# valve_schematic.net
KiCad netlist of a schematic drawn in Altium Designer
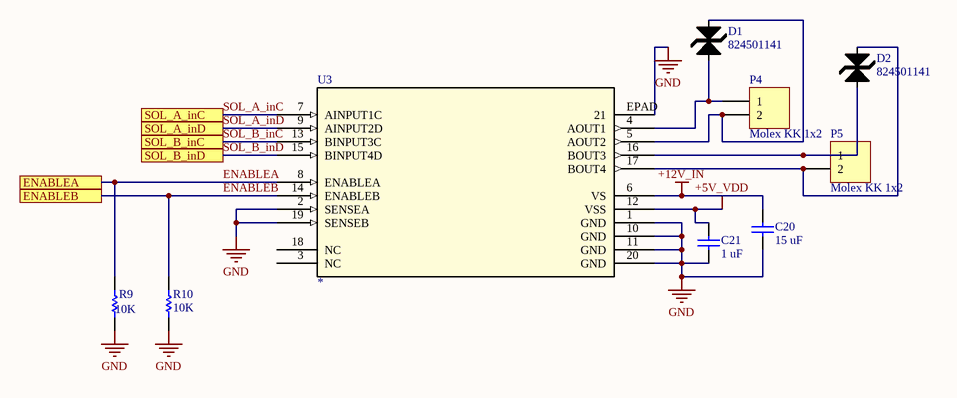
[diagram p0: valve_schematic.SchDoc]

(export (version "E")
  (design (tool "Eeschema 10.0.6"))
  (components
    (comp (ref "C20")
      (value "15 uF")
      (footprint "C0603")
      (description "0603 Capacitor")
      (libsource (lib "PARSEC") (part "C0603"))
    )
    (comp (ref "C21")
      (value "1 uF")
      (footprint "C0603")
      (description "0603 Capacitor")
      (libsource (lib "PARSEC") (part "C0603"))
    )
    (comp (ref "D1")
      (value "824501141")
      (footprint "DIODE-SMA")
      (description "TVS DIODE 14V 23.2V DO214AC")
      (libsource (lib "PARSEC") (part "824501141"))
    )
    (comp (ref "D2")
      (value "824501141")
      (footprint "DIODE-SMA")
      (description "TVS DIODE 14V 23.2V DO214AC")
      (libsource (lib "PARSEC") (part "824501141"))
    )
    (comp (ref "P4")
      (value "Molex KK 1x2")
      (footprint "Molex KK 2x1")
      (description "1x2 Molex KK Connector")
      (libsource (lib "PARSEC") (part "Molex KK 1x2"))
    )
    (comp (ref "P5")
      (value "Molex KK 1x2")
      (footprint "Molex KK 2x1")
      (description "1x2 Molex KK Connector")
      (libsource (lib "PARSEC") (part "Molex KK 1x2"))
    )
    (comp (ref "R9")
      (value "10K")
      (footprint "R0805")
      (description "RESISTOR 0805")
      (libsource (lib "PARSEC(1)") (part "R0805"))
    )
    (comp (ref "R10")
      (value "10K")
      (footprint "R0805")
      (description "RESISTOR 0805")
      (libsource (lib "PARSEC(1)") (part "R0805"))
    )
    (comp (ref "U3")
      (value "*")
      (footprint "PowerSO-20")
      (description "Imported")
      (fields (field (name "MANUFACTURER_PART_NUMBER") "L298P013TR"))
      (libsource (lib "PARSEC(1)") (part "L298P013TR"))
    )
  )
  (nets
    (net (code "1") (name "+5V_VDD") (class "Default")
      (node (ref "C21") (pin "1") (pinfunction "1_1") (pintype "passive"))
      (node (ref "U3") (pin "12") (pinfunction "VSS_12") (pintype "power_in"))
    )
    (net (code "2") (name "+12V_IN") (class "Default")
      (node (ref "C20") (pin "1") (pinfunction "1_1") (pintype "passive"))
      (node (ref "U3") (pin "6") (pinfunction "VS_6") (pintype "power_in"))
    )
    (net (code "3") (name "/ENABLEA") (class "Default")
      (node (ref "R9") (pin "2") (pinfunction "2_2") (pintype "passive"))
      (node (ref "U3") (pin "8") (pinfunction "ENABLEA_8") (pintype "input"))
    )
    (net (code "4") (name "/ENABLEB") (class "Default")
      (node (ref "R10") (pin "2") (pinfunction "2_2") (pintype "passive"))
      (node (ref "U3") (pin "14") (pinfunction "ENABLEB_14") (pintype "input"))
    )
    (net (code "5") (name "/SOL_A_inC") (class "Default")
      (node (ref "U3") (pin "7") (pinfunction "AINPUT1C_7") (pintype "input"))
    )
    (net (code "6") (name "/SOL_A_inD") (class "Default")
      (node (ref "U3") (pin "9") (pinfunction "AINPUT2D_9") (pintype "input"))
    )
    (net (code "7") (name "/SOL_B_inC") (class "Default")
      (node (ref "U3") (pin "13") (pinfunction "BINPUT3C_13") (pintype "input"))
    )
    (net (code "8") (name "/SOL_B_inD") (class "Default")
      (node (ref "U3") (pin "15") (pinfunction "BINPUT4D_15") (pintype "input"))
    )
    (net (code "9") (name "GND") (class "Default")
      (node (ref "C20") (pin "2") (pinfunction "2_2") (pintype "passive"))
      (node (ref "C21") (pin "2") (pinfunction "2_2") (pintype "passive"))
      (node (ref "R10") (pin "1") (pinfunction "1_1") (pintype "passive"))
      (node (ref "R9") (pin "1") (pinfunction "1_1") (pintype "passive"))
      (node (ref "U3") (pin "1") (pinfunction "GND_1") (pintype "passive"))
      (node (ref "U3") (pin "10") (pinfunction "GND_10") (pintype "passive"))
      (node (ref "U3") (pin "11") (pinfunction "GND_11") (pintype "passive"))
      (node (ref "U3") (pin "19") (pinfunction "SENSEB_19") (pintype "input"))
      (node (ref "U3") (pin "2") (pinfunction "SENSEA_2") (pintype "input"))
      (node (ref "U3") (pin "20") (pinfunction "GND_20") (pintype "passive"))
      (node (ref "U3") (pin "EPAD") (pinfunction "21_EPAD") (pintype "passive"))
    )
    (net (code "10") (name "Net-(U3-AOUT1)") (class "Default")
      (node (ref "D1") (pin "A") (pinfunction "A_A") (pintype "passive"))
      (node (ref "P4") (pin "1") (pinfunction "1_1") (pintype "passive"))
      (node (ref "U3") (pin "4") (pinfunction "AOUT1_4") (pintype "output"))
    )
    (net (code "11") (name "Net-(U3-AOUT2)") (class "Default")
      (node (ref "D1") (pin "K") (pinfunction "K_K") (pintype "passive"))
      (node (ref "P4") (pin "2") (pinfunction "2_2") (pintype "passive"))
      (node (ref "U3") (pin "5") (pinfunction "AOUT2_5") (pintype "output"))
    )
    (net (code "12") (name "Net-(U3-BOUT3)") (class "Default")
      (node (ref "D2") (pin "A") (pinfunction "A_A") (pintype "passive"))
      (node (ref "P5") (pin "1") (pinfunction "1_1") (pintype "passive"))
      (node (ref "U3") (pin "16") (pinfunction "BOUT3_16") (pintype "output"))
    )
    (net (code "13") (name "Net-(U3-BOUT4)") (class "Default")
      (node (ref "D2") (pin "K") (pinfunction "K_K") (pintype "passive"))
      (node (ref "P5") (pin "2") (pinfunction "2_2") (pintype "passive"))
      (node (ref "U3") (pin "17") (pinfunction "BOUT4_17") (pintype "output"))
    )
    (net (code "14") (name "unconnected-(U3-NC-Pad3)") (class "Default")
      (node (ref "U3") (pin "3") (pinfunction "NC_3") (pintype "passive"))
    )
    (net (code "15") (name "unconnected-(U3-NC-Pad18)") (class "Default")
      (node (ref "U3") (pin "18") (pinfunction "NC_18") (pintype "passive"))
    )
  )
)
